# Rpi_1_wire.net
KiCad netlist of a schematic drawn in EAGLE
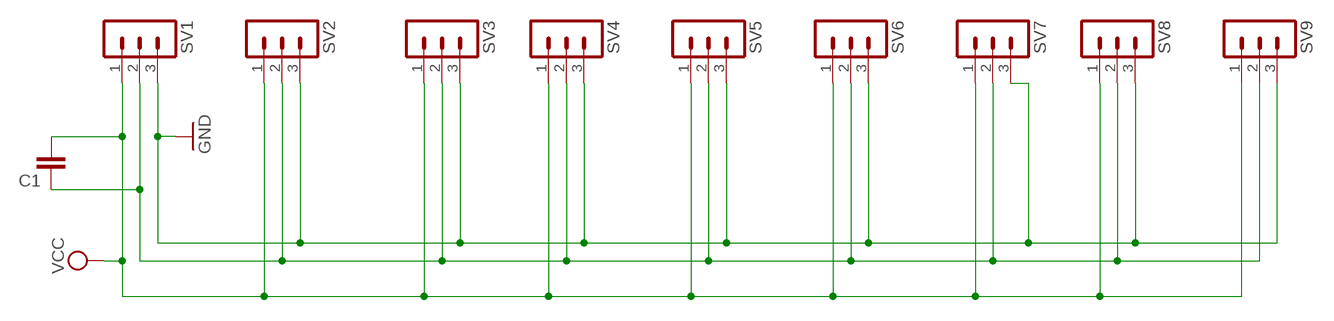
[diagram p0: schematic, sheet 1]

(export (version "E")
  (design (tool "Eeschema 10.0.6"))
  (components
    (comp (ref "C1")
      (value "C-EUC0805")
      (footprint "eagle-import:C0805")
      (libsource (lib "eagle-import") (part "C-EUC0805"))
    )
    (comp (ref "SV1")
      (value "MA03-1")
      (footprint "eagle-import:MA03-1")
      (libsource (lib "eagle-import") (part "MA03-1"))
    )
    (comp (ref "SV2")
      (value "MA03-1")
      (footprint "eagle-import:MA03-1")
      (libsource (lib "eagle-import") (part "MA03-1"))
    )
    (comp (ref "SV3")
      (value "MA03-1")
      (footprint "eagle-import:MA03-1")
      (libsource (lib "eagle-import") (part "MA03-1"))
    )
    (comp (ref "SV4")
      (value "MA03-1")
      (footprint "eagle-import:MA03-1")
      (libsource (lib "eagle-import") (part "MA03-1"))
    )
    (comp (ref "SV5")
      (value "MA03-1")
      (footprint "eagle-import:MA03-1")
      (libsource (lib "eagle-import") (part "MA03-1"))
    )
    (comp (ref "SV6")
      (value "MA03-1")
      (footprint "eagle-import:MA03-1")
      (libsource (lib "eagle-import") (part "MA03-1"))
    )
    (comp (ref "SV7")
      (value "MA03-1")
      (footprint "eagle-import:MA03-1")
      (libsource (lib "eagle-import") (part "MA03-1"))
    )
    (comp (ref "SV8")
      (value "MA03-1")
      (footprint "eagle-import:MA03-1")
      (libsource (lib "eagle-import") (part "MA03-1"))
    )
    (comp (ref "SV9")
      (value "MA03-1")
      (footprint "eagle-import:MA03-1")
      (libsource (lib "eagle-import") (part "MA03-1"))
    )
  )
  (nets
    (net (code "1") (name "GND") (class "Default")
      (node (ref "SV1") (pin "3") (pinfunction "3_3") (pintype "passive"))
      (node (ref "SV2") (pin "3") (pinfunction "3_3") (pintype "passive"))
      (node (ref "SV3") (pin "3") (pinfunction "3_3") (pintype "passive"))
      (node (ref "SV4") (pin "3") (pinfunction "3_3") (pintype "passive"))
      (node (ref "SV5") (pin "3") (pinfunction "3_3") (pintype "passive"))
      (node (ref "SV6") (pin "3") (pinfunction "3_3") (pintype "passive"))
      (node (ref "SV7") (pin "3") (pinfunction "3_3") (pintype "passive"))
      (node (ref "SV8") (pin "3") (pinfunction "3_3") (pintype "passive"))
      (node (ref "SV9") (pin "3") (pinfunction "3_3") (pintype "passive"))
    )
    (net (code "2") (name "Net-(C1-Pad1)") (class "Default")
      (node (ref "C1") (pin "1") (pinfunction "1_1") (pintype "passive"))
      (node (ref "SV1") (pin "2") (pinfunction "2_2") (pintype "passive"))
      (node (ref "SV2") (pin "2") (pinfunction "2_2") (pintype "passive"))
      (node (ref "SV3") (pin "2") (pinfunction "2_2") (pintype "passive"))
      (node (ref "SV4") (pin "2") (pinfunction "2_2") (pintype "passive"))
      (node (ref "SV5") (pin "2") (pinfunction "2_2") (pintype "passive"))
      (node (ref "SV6") (pin "2") (pinfunction "2_2") (pintype "passive"))
      (node (ref "SV7") (pin "2") (pinfunction "2_2") (pintype "passive"))
      (node (ref "SV8") (pin "2") (pinfunction "2_2") (pintype "passive"))
      (node (ref "SV9") (pin "2") (pinfunction "2_2") (pintype "passive"))
    )
    (net (code "3") (name "VCC") (class "Default")
      (node (ref "C1") (pin "2") (pinfunction "2_2") (pintype "passive"))
      (node (ref "SV1") (pin "1") (pinfunction "1_1") (pintype "passive"))
      (node (ref "SV2") (pin "1") (pinfunction "1_1") (pintype "passive"))
      (node (ref "SV3") (pin "1") (pinfunction "1_1") (pintype "passive"))
      (node (ref "SV4") (pin "1") (pinfunction "1_1") (pintype "passive"))
      (node (ref "SV5") (pin "1") (pinfunction "1_1") (pintype "passive"))
      (node (ref "SV6") (pin "1") (pinfunction "1_1") (pintype "passive"))
      (node (ref "SV7") (pin "1") (pinfunction "1_1") (pintype "passive"))
      (node (ref "SV8") (pin "1") (pinfunction "1_1") (pintype "passive"))
      (node (ref "SV9") (pin "1") (pinfunction "1_1") (pintype "passive"))
    )
  )
)
